# ESP32.net
KiCad netlist of a schematic drawn in Altium Designer
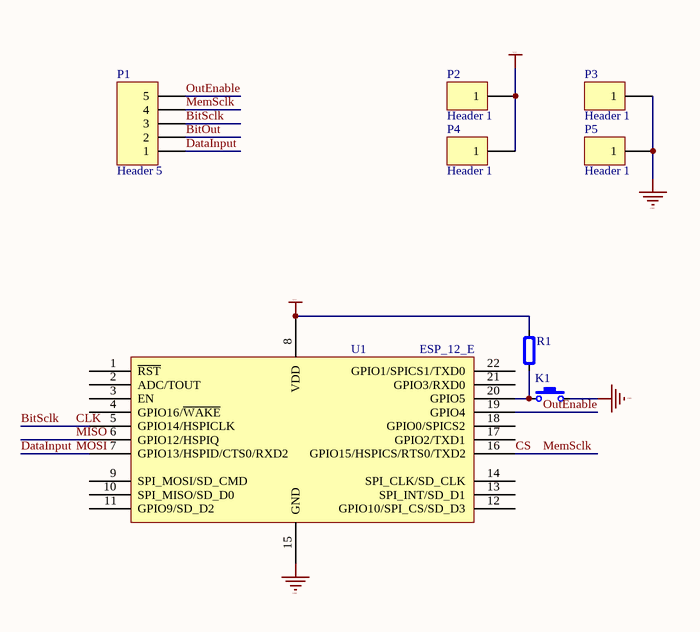
[diagram p0: ESP32.SchDoc]

(export (version "E")
  (design (tool "Eeschema 10.0.6"))
  (components
    (comp (ref "K1")
      (value "TACT 2P")
      (footprint "ButtonTACT_3x6x2.5_180")
      (description "Button")
      (libsource (lib "EspPov") (part "ButtonTACT_3x6x2.5_180"))
    )
    (comp (ref "P1")
      (value "Header 5")
      (footprint "HDR1X5_SOP")
      (description "Header, 5-Pin")
      (fields (field (name "PUBLISHER") "Altium Limited"))
      (libsource (lib "EspPov") (part "Header 5"))
    )
    (comp (ref "P2")
      (value "Header 1")
      (footprint "HDR1X1_SOP")
      (description "Header, 1-Pin")
      (fields (field (name "PUBLISHER") "Altium Limited"))
      (libsource (lib "EspPov") (part "Header 1"))
    )
    (comp (ref "P3")
      (value "Header 1")
      (footprint "HDR1X1_SOP")
      (description "Header, 1-Pin")
      (fields (field (name "PUBLISHER") "Altium Limited"))
      (libsource (lib "EspPov") (part "Header 1"))
    )
    (comp (ref "P4")
      (value "Header 1")
      (footprint "HDR1X1_SOP")
      (description "Header, 1-Pin")
      (fields (field (name "PUBLISHER") "Altium Limited"))
      (libsource (lib "EspPov") (part "Header 1"))
    )
    (comp (ref "P5")
      (value "Header 1")
      (footprint "HDR1X1_SOP")
      (description "Header, 1-Pin")
      (fields (field (name "PUBLISHER") "Altium Limited"))
      (libsource (lib "EspPov") (part "Header 1"))
    )
    (comp (ref "R1")
      (value "R0805")
      (footprint "PCB_PassiveRes:RES_0805")
      (description "Resistor")
      (libsource (lib "EspPov") (part "Res_0805"))
    )
    (comp (ref "U1")
      (value "ESP_12_E")
      (footprint "ESP_12_E")
      (description "ESP-12 Wi-Fi Module by AI-Thinker")
      (libsource (lib "EspPov") (part "ESP_12_E"))
    )
  )
  (nets
    (net (code "1") (name "/BitOut") (class "Default")
      (node (ref "P1") (pin "2") (pinfunction "2_2") (pintype "passive"))
    )
    (net (code "2") (name "/BitSclk") (class "Default")
      (node (ref "P1") (pin "3") (pinfunction "3_3") (pintype "passive"))
      (node (ref "U1") (pin "5") (pinfunction "GPIO14/HSPICLK_5") (pintype "passive"))
    )
    (net (code "3") (name "/CS") (class "Default")
      (node (ref "P1") (pin "4") (pinfunction "4_4") (pintype "passive"))
      (node (ref "U1") (pin "16") (pinfunction "GPIO15/HSPICS/RTS0/TXD2_16") (pintype "passive"))
    )
    (net (code "4") (name "/DataInput") (class "Default")
      (node (ref "P1") (pin "1") (pinfunction "1_1") (pintype "passive"))
      (node (ref "U1") (pin "7") (pinfunction "GPIO13/HSPID/CTS0/RXD2_7") (pintype "passive"))
    )
    (net (code "5") (name "/MISO") (class "Default")
      (node (ref "U1") (pin "6") (pinfunction "GPIO12/HSPIQ_6") (pintype "passive"))
    )
    (net (code "6") (name "/OutEnable") (class "Default")
      (node (ref "P1") (pin "5") (pinfunction "5_5") (pintype "passive"))
      (node (ref "U1") (pin "19") (pinfunction "GPIO4_19") (pintype "passive"))
    )
    (net (code "7") (name "GND") (class "Default")
      (node (ref "K1") (pin "2") (pinfunction "2_2") (pintype "passive"))
      (node (ref "P3") (pin "1") (pinfunction "1_1") (pintype "passive"))
      (node (ref "P5") (pin "1") (pinfunction "1_1") (pintype "passive"))
      (node (ref "U1") (pin "15") (pinfunction "GND_15") (pintype "passive"))
    )
    (net (code "8") (name "Net-(U1-GPIO5)") (class "Default")
      (node (ref "K1") (pin "1") (pinfunction "1_1") (pintype "passive"))
      (node (ref "R1") (pin "1") (pinfunction "1_1") (pintype "passive"))
      (node (ref "U1") (pin "20") (pinfunction "GPIO5_20") (pintype "passive"))
    )
    (net (code "9") (name "VCC") (class "Default")
      (node (ref "P2") (pin "1") (pinfunction "1_1") (pintype "passive"))
      (node (ref "P4") (pin "1") (pinfunction "1_1") (pintype "passive"))
      (node (ref "R1") (pin "2") (pinfunction "2_2") (pintype "passive"))
      (node (ref "U1") (pin "8") (pinfunction "VDD_8") (pintype "passive"))
    )
    (net (code "10") (name "unconnected-(U1-ADC{slash}TOUT-Pad2)") (class "Default")
      (node (ref "U1") (pin "2") (pinfunction "ADC/TOUT_2") (pintype "passive"))
    )
    (net (code "11") (name "unconnected-(U1-EN-Pad3)") (class "Default")
      (node (ref "U1") (pin "3") (pinfunction "EN_3") (pintype "passive"))
    )
    (net (code "12") (name "unconnected-(U1-GPIO0{slash}SPICS2-Pad18)") (class "Default")
      (node (ref "U1") (pin "18") (pinfunction "GPIO0/SPICS2_18") (pintype "passive"))
    )
    (net (code "13") (name "unconnected-(U1-GPIO1{slash}SPICS1{slash}TXD0-Pad22)") (class "Default")
      (node (ref "U1") (pin "22") (pinfunction "GPIO1/SPICS1/TXD0_22") (pintype "passive"))
    )
    (net (code "14") (name "unconnected-(U1-GPIO2{slash}TXD1-Pad17)") (class "Default")
      (node (ref "U1") (pin "17") (pinfunction "GPIO2/TXD1_17") (pintype "passive"))
    )
    (net (code "15") (name "unconnected-(U1-GPIO3{slash}RXD0-Pad21)") (class "Default")
      (node (ref "U1") (pin "21") (pinfunction "GPIO3/RXD0_21") (pintype "passive"))
    )
    (net (code "16") (name "unconnected-(U1-GPIO9{slash}SD_D2-Pad11)") (class "Default")
      (node (ref "U1") (pin "11") (pinfunction "GPIO9/SD_D2_11") (pintype "passive"))
    )
    (net (code "17") (name "unconnected-(U1-GPIO10{slash}SPI_CS{slash}SD_D3-Pad12)") (class "Default")
      (node (ref "U1") (pin "12") (pinfunction "GPIO10/SPI_CS/SD_D3_12") (pintype "passive"))
    )
    (net (code "18") (name "unconnected-(U1-GPIO16{slash}~{WAKE}-Pad4)") (class "Default")
      (node (ref "U1") (pin "4") (pinfunction "GPIO16/~{WAKE}_4") (pintype "passive"))
    )
    (net (code "19") (name "unconnected-(U1-SPI_CLK{slash}SD_CLK-Pad14)") (class "Default")
      (node (ref "U1") (pin "14") (pinfunction "SPI_CLK/SD_CLK_14") (pintype "passive"))
    )
    (net (code "20") (name "unconnected-(U1-SPI_INT{slash}SD_D1-Pad13)") (class "Default")
      (node (ref "U1") (pin "13") (pinfunction "SPI_INT/SD_D1_13") (pintype "passive"))
    )
    (net (code "21") (name "unconnected-(U1-SPI_MISO{slash}SD_D0-Pad10)") (class "Default")
      (node (ref "U1") (pin "10") (pinfunction "SPI_MISO/SD_D0_10") (pintype "passive"))
    )
    (net (code "22") (name "unconnected-(U1-SPI_MOSI{slash}SD_CMD-Pad9)") (class "Default")
      (node (ref "U1") (pin "9") (pinfunction "SPI_MOSI/SD_CMD_9") (pintype "passive"))
    )
    (net (code "23") (name "unconnected-(U1-~{RST}-Pad1)") (class "Default")
      (node (ref "U1") (pin "1") (pinfunction "~{RST}_1") (pintype "passive"))
    )
  )
)
